# RF.net
KiCad netlist of a schematic drawn in Altium Designer
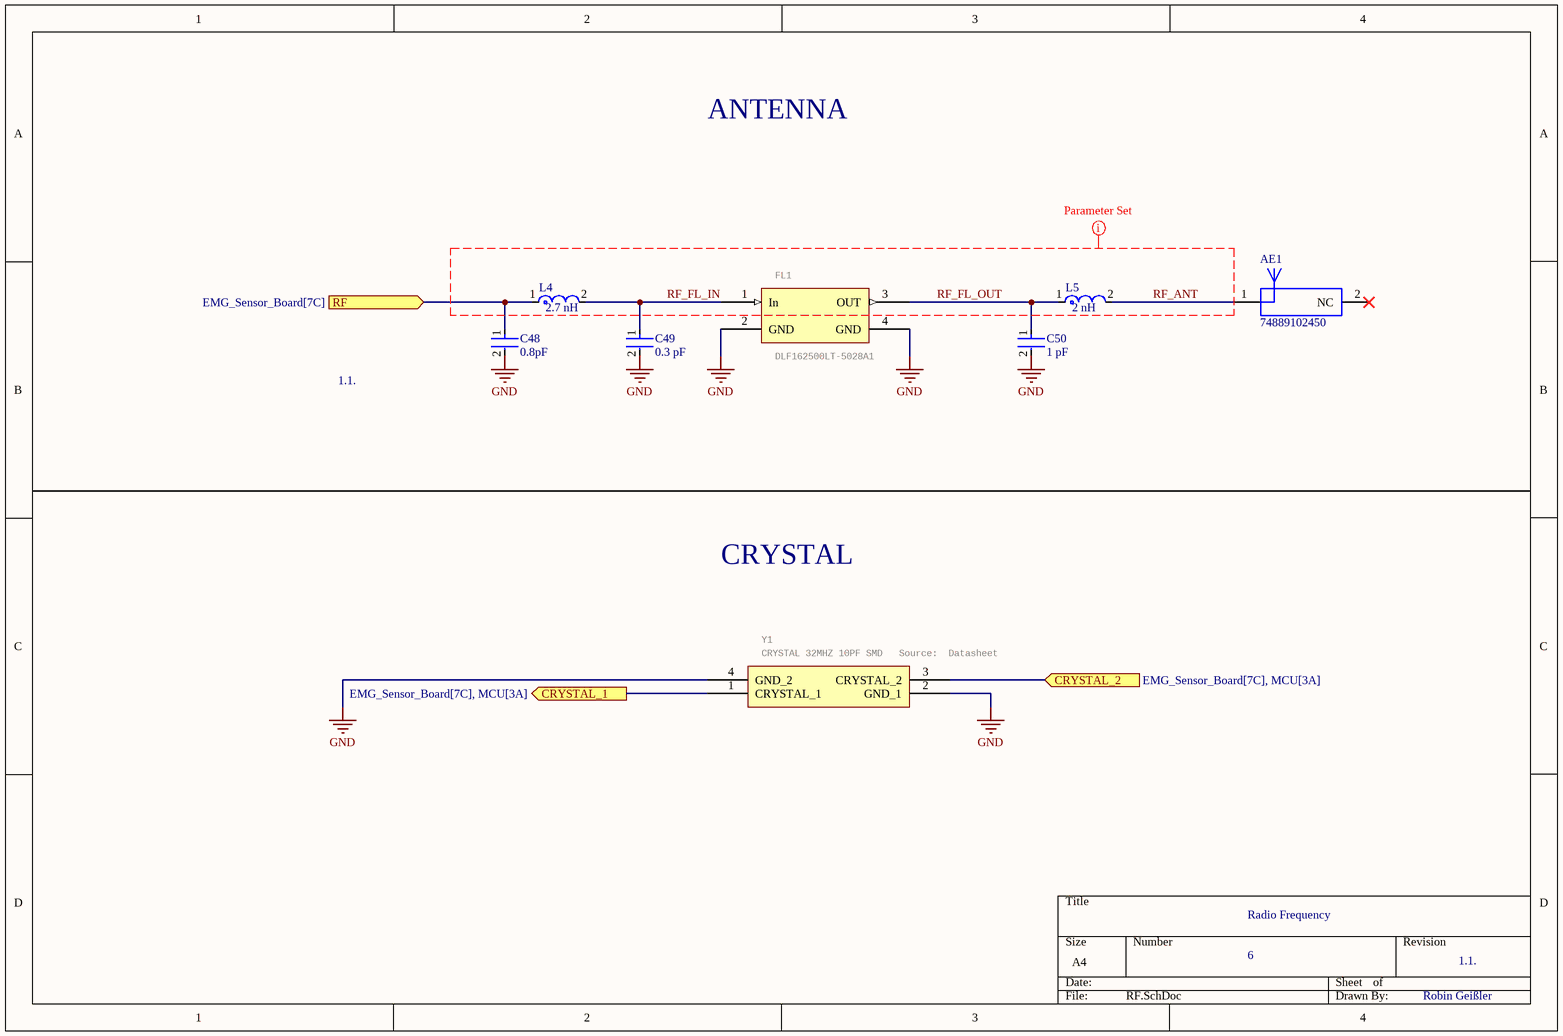
[diagram p0: RF.SchDoc]

(export (version "E")
  (design (tool "Eeschema 10.0.6"))
  (components
    (comp (ref "AE1")
      (value "74889102450")
      (footprint "74889102450")
      (description "74889102450 Chip Antenna, 2.45Ghz, 9Mm X 2Mm X 1Mm Rohs Compliant: Yes")
      (libsource (lib "Altium Content Vault") (part "74889102450"))
    )
    (comp (ref "C48")
      (value "0.8pF")
      (footprint "FP-GCM188-0_1-IPC_C")
      (description "Ceramic Capacitor for Automotive 0.8pF  ±0.1pF 100VDC C0G 0603 Paper T/R")
      (libsource (lib "Altium Content Vault") (part "02cd4be3c70576c341d710602a673aa"))
    )
    (comp (ref "C49")
      (value "0.3 pF")
      (footprint "FP-GQM187-0_15-IPC_A")
      (description "Ceramic Capacitor 0.3pF ±0.05pF 250VDC C0G 0603 Paper T/R")
      (libsource (lib "Altium Content Vault") (part "02cd4be3c70576c341d710602a673aa"))
    )
    (comp (ref "C50")
      (value "1 pF")
      (footprint "FP-C0603C-CF-MFG")
      (description "CAP CER 1PF 50V C0G/NP0 0603")
      (fields (field (name "TOLERANCE") "0.25 pF") (field (name "MANUFACTURER") "KEMET"))
      (libsource (lib "Altium Content Vault") (part "b4654b650e69147ec39a6b967a45e02"))
    )
    (comp (ref "FL1")
      (value "DLF162500LT-5028A1")
      (footprint "DLF162500LT5028A1")
      (description "Signal Conditioning LTCC LOW PASS FLTR 2400-2500MHz   Source:  Datasheet")
      (fields (field (name "MOUSER_PART_NUMBER") "810-DLF16250LT5028A1"))
      (libsource (lib "EMG_Sensor") (part "DLF162500LT-5028A1"))
    )
    (comp (ref "L4")
      (value "2.7 nH")
      (footprint "FP-LQG15HH_02-IPC_C")
      (description "Multilayer type RF Inductor 2.7nH ±0.3nH 0.12Ω 800mA 0402")
      (libsource (lib "Altium Content Vault") (part "4cc4b267dca4c8e51f7102f422741d8"))
    )
    (comp (ref "L5")
      (value "2 nH")
      (footprint "FP-LQP03TG_02-IPC_A")
      (description "Film type RF Inductor 2nH ±0.1nH 600mA 0.15Ω 0201 (0603)")
      (libsource (lib "Altium Content Vault") (part "4cc4b267dca4c8e51f7102f422741d8"))
    )
    (comp (ref "Y1")
      (value "CRYSTAL 32MHZ 10PF SMD   Source:  Datasheet")
      (footprint "NX2016SA32MEXS00ACS06465")
      (fields
        (field (name "MANUFACTURER_PART_NUMBER") "NX2016SA-32M-EXS00A-CS06465")
        (field (name "MOUSER_PART_NUMBER") "344-NX2016SA32S06465")
      )
      (libsource (lib "EMG_Sensor") (part "NX2016SA-32M-EXS00A-CS06465"))
    )
  )
  (nets
    (net (code "1") (name "/CRYSTAL_1") (class "Default")
      (node (ref "Y1") (pin "1") (pinfunction "CRYSTAL_1_1") (pintype "passive"))
    )
    (net (code "2") (name "/CRYSTAL_2") (class "Default")
      (node (ref "Y1") (pin "3") (pinfunction "CRYSTAL_2_3") (pintype "passive"))
    )
    (net (code "3") (name "/RF") (class "Default")
      (node (ref "C48") (pin "1") (pinfunction "1_1") (pintype "passive"))
      (node (ref "L4") (pin "1") (pinfunction "1_1") (pintype "passive"))
    )
    (net (code "4") (name "/RF_ANT") (class "Default")
      (node (ref "AE1") (pin "1") (pinfunction "Feed_1") (pintype "passive"))
      (node (ref "L5") (pin "2") (pinfunction "2_2") (pintype "passive"))
    )
    (net (code "5") (name "/RF_FL_IN") (class "Default")
      (node (ref "C49") (pin "1") (pinfunction "1_1") (pintype "passive"))
      (node (ref "FL1") (pin "1") (pinfunction "In_1") (pintype "input"))
      (node (ref "L4") (pin "2") (pinfunction "2_2") (pintype "passive"))
    )
    (net (code "6") (name "/RF_FL_OUT") (class "Default")
      (node (ref "C50") (pin "1") (pinfunction "1_1") (pintype "passive"))
      (node (ref "FL1") (pin "3") (pinfunction "OUT_3") (pintype "output"))
      (node (ref "L5") (pin "1") (pinfunction "1_1") (pintype "passive"))
    )
    (net (code "7") (name "GND") (class "Default")
      (node (ref "C48") (pin "2") (pinfunction "2_2") (pintype "passive"))
      (node (ref "C49") (pin "2") (pinfunction "2_2") (pintype "passive"))
      (node (ref "C50") (pin "2") (pinfunction "2_2") (pintype "passive"))
      (node (ref "FL1") (pin "2") (pinfunction "GND_2") (pintype "passive"))
      (node (ref "FL1") (pin "4") (pinfunction "GND_4") (pintype "passive"))
      (node (ref "Y1") (pin "2") (pinfunction "GND_1_2") (pintype "passive"))
      (node (ref "Y1") (pin "4") (pinfunction "GND_2_4") (pintype "passive"))
    )
    (net (code "8") (name "unconnected-(AE1-NC-Pad2)") (class "Default")
      (node (ref "AE1") (pin "2") (pinfunction "NC_2") (pintype "passive+no_connect"))
    )
  )
)
